# LNA.net
KiCad netlist of a schematic drawn in EAGLE
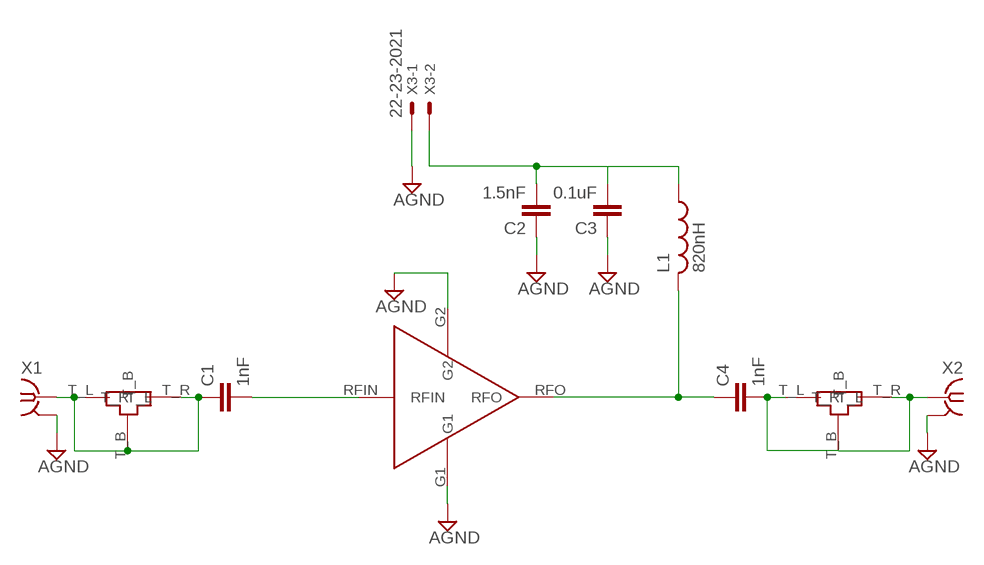
[diagram p0: schematic, sheet 1]

(export (version "E")
  (design (tool "Eeschema 10.0.6"))
  (components
    (comp (ref "C1")
      (value "1nF")
      (footprint "eagle-import:C0603")
      (libsource (lib "eagle-import") (part "C-EUC0603"))
    )
    (comp (ref "C2")
      (value "1.5nF")
      (footprint "eagle-import:C0603")
      (libsource (lib "eagle-import") (part "C-EUC0603"))
    )
    (comp (ref "C3")
      (value "0.1uF")
      (footprint "eagle-import:C0603")
      (libsource (lib "eagle-import") (part "C-EUC0603"))
    )
    (comp (ref "C4")
      (value "1nF")
      (footprint "eagle-import:C0603")
      (libsource (lib "eagle-import") (part "C-EUC0603"))
    )
    (comp (ref "IN1")
      (value "TEE_TL1")
      (footprint "eagle-import:TEE_TL1")
      (libsource (lib "eagle-import") (part "TEE_TL1"))
    )
    (comp (ref "L1")
      (value "820nH")
      (footprint "eagle-import:L3230M")
      (libsource (lib "eagle-import") (part "L-USL3230M"))
    )
    (comp (ref "OUT2")
      (value "TEE_TL1")
      (footprint "eagle-import:TEE_TL1")
      (libsource (lib "eagle-import") (part "TEE_TL1"))
    )
    (comp (ref "U$1")
      (value "PSA4-5043+")
      (footprint "eagle-import:PSA4-5043+")
      (libsource (lib "eagle-import") (part "PSA4-5043+"))
    )
    (comp (ref "X1")
      (value "SMA-142-0711-821/826")
      (footprint "eagle-import:J502-ND-142-0711-821_826")
      (fields (field (name "MF") "JOHNSON COMPONENTS") (field (name "MPN") "142-0711-821"))
      (libsource (lib "eagle-import") (part "SMA-142-0711-821/826"))
    )
    (comp (ref "X2")
      (value "SMA-142-0711-821/826")
      (footprint "eagle-import:J502-ND-142-0711-821_826")
      (fields (field (name "MF") "JOHNSON COMPONENTS") (field (name "MPN") "142-0711-821"))
      (libsource (lib "eagle-import") (part "SMA-142-0711-821/826"))
    )
    (comp (ref "X3")
      (value "22-23-2021")
      (footprint "eagle-import:22-23-2021")
      (fields (field (name "MF") "MOLEX"))
      (libsource (lib "eagle-import") (part "22-23-2021"))
    )
  )
  (nets
    (net (code "1") (name "AGND") (class "Default")
      (node (ref "C2") (pin "1") (pinfunction "1_1") (pintype "passive"))
      (node (ref "C3") (pin "1") (pinfunction "1_1") (pintype "passive"))
      (node (ref "U$1") (pin "G1") (pinfunction "G1_G1") (pintype "bidirectional"))
      (node (ref "U$1") (pin "G2") (pinfunction "G2_G2") (pintype "bidirectional"))
      (node (ref "X1") (pin "G@1") (pinfunction "2_G@1") (pintype "passive"))
      (node (ref "X1") (pin "G@2") (pinfunction "2_G@2") (pintype "passive"))
      (node (ref "X1") (pin "G@3") (pinfunction "2_G@3") (pintype "passive"))
      (node (ref "X1") (pin "G@4") (pinfunction "2_G@4") (pintype "passive"))
      (node (ref "X2") (pin "G@1") (pinfunction "2_G@1") (pintype "passive"))
      (node (ref "X2") (pin "G@2") (pinfunction "2_G@2") (pintype "passive"))
      (node (ref "X2") (pin "G@3") (pinfunction "2_G@3") (pintype "passive"))
      (node (ref "X2") (pin "G@4") (pinfunction "2_G@4") (pintype "passive"))
      (node (ref "X3") (pin "1") (pinfunction "S_1") (pintype "passive"))
    )
    (net (code "2") (name "Net-(C1-Pad1)") (class "Default")
      (node (ref "C1") (pin "1") (pinfunction "1_1") (pintype "passive"))
      (node (ref "IN1") (pin "T_B") (pinfunction "T_B_T_B") (pintype "bidirectional"))
      (node (ref "IN1") (pin "T_L") (pinfunction "T_L_T_L") (pintype "bidirectional"))
      (node (ref "IN1") (pin "T_R") (pinfunction "T_R_T_R") (pintype "bidirectional"))
      (node (ref "X1") (pin "1") (pinfunction "1_1") (pintype "passive"))
    )
    (net (code "3") (name "Net-(C1-Pad2)") (class "Default")
      (node (ref "C1") (pin "2") (pinfunction "2_2") (pintype "passive"))
      (node (ref "U$1") (pin "RFIN") (pinfunction "RFIN_RFIN") (pintype "bidirectional"))
    )
    (net (code "4") (name "Net-(C4-Pad1)") (class "Default")
      (node (ref "C4") (pin "1") (pinfunction "1_1") (pintype "passive"))
      (node (ref "L1") (pin "2") (pinfunction "2_2") (pintype "passive"))
      (node (ref "U$1") (pin "RFO") (pinfunction "RFO_RFO") (pintype "bidirectional"))
    )
    (net (code "5") (name "Net-(C4-Pad2)") (class "Default")
      (node (ref "C4") (pin "2") (pinfunction "2_2") (pintype "passive"))
      (node (ref "OUT2") (pin "T_B") (pinfunction "T_B_T_B") (pintype "bidirectional"))
      (node (ref "OUT2") (pin "T_L") (pinfunction "T_L_T_L") (pintype "bidirectional"))
      (node (ref "OUT2") (pin "T_R") (pinfunction "T_R_T_R") (pintype "bidirectional"))
      (node (ref "X2") (pin "1") (pinfunction "1_1") (pintype "passive"))
    )
    (net (code "6") (name "Net-(X3B-S)") (class "Default")
      (node (ref "C2") (pin "2") (pinfunction "2_2") (pintype "passive"))
      (node (ref "C3") (pin "2") (pinfunction "2_2") (pintype "passive"))
      (node (ref "L1") (pin "1") (pinfunction "1_1") (pintype "passive"))
      (node (ref "X3") (pin "2") (pinfunction "S_2") (pintype "passive"))
    )
  )
)
